# Sheet1.net
KiCad netlist of a schematic drawn in Altium Designer
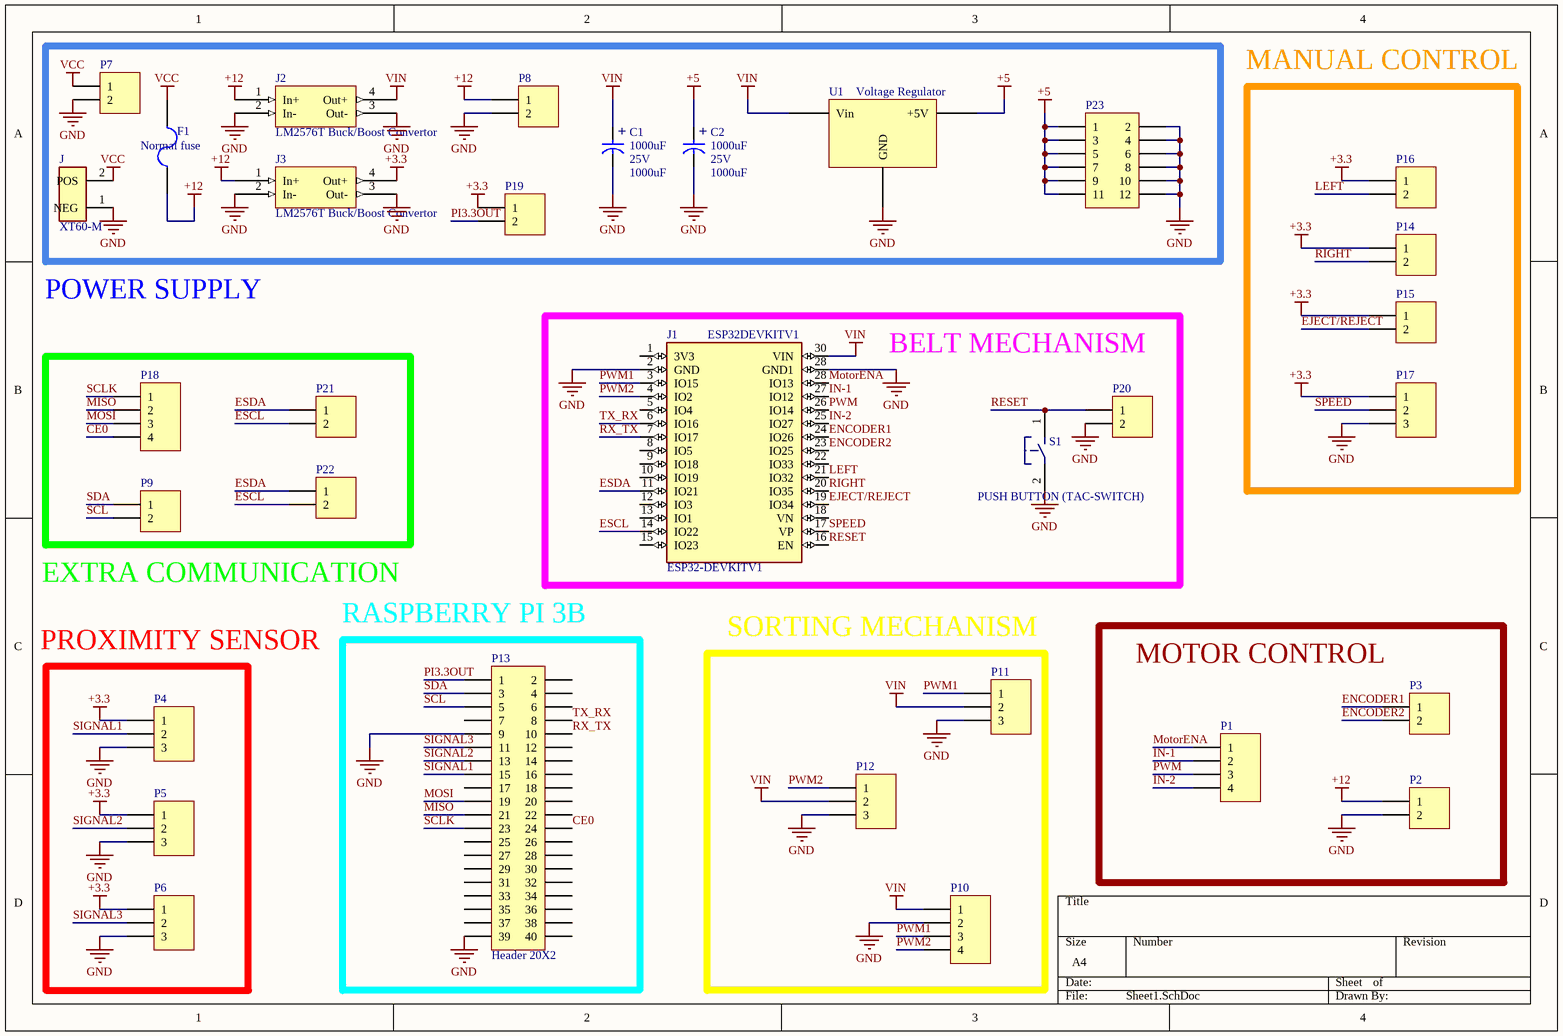
[diagram p0: Sheet1.SchDoc]

(export (version "E")
  (design (tool "Eeschema 10.0.6"))
  (components
    (comp (ref "C1")
      (value "1000uF")
      (footprint "SELF_CAP_THT5MM")
      (fields (field (name "VOLT") "25V") (field (name "ALTIUM_VALUE") "1000uF"))
      (libsource (lib "Webinar") (part "CAPACITOR (ELECTROLYTIC)"))
    )
    (comp (ref "C2")
      (value "1000uF")
      (footprint "SELF_CAP_THT5MM")
      (fields (field (name "VOLT") "25V") (field (name "ALTIUM_VALUE") "1000uF"))
      (libsource (lib "Webinar") (part "CAPACITOR (ELECTROLYTIC)"))
    )
    (comp (ref "F1")
      (value "Normal fuse")
      (footprint "MY_FUSE")
      (fields (field (name "ASID PART NUMBER") "Fuse-AS"))
      (libsource (lib "Mylib Rev 4") (part "Fuse"))
    )
    (comp (ref "J")
      (value "XT60-M")
      (footprint "AMASS_XT60-M")
      (description "Plug; DC supply; XT60; male; PIN: 2; for cable; soldered; 30A; 500V")
      (fields (field (name "MF") "AMASS"))
      (libsource (lib "myLibrary") (part "XT60-M"))
    )
    (comp (ref "J1")
      (value "ESP32DEVKITV1")
      (footprint "ESP32-DEVKITV1")
      (fields (field (name "MP") "ESP32 DEVKIT V1") (field (name "MF") "Do it"))
      (libsource (lib "ESP32DEVKITV1") (part "ESP32DEVKITV1"))
    )
    (comp (ref "J2")
      (value "LM2576T Buck/Boost Convertor")
      (footprint "LM2596 MODULE")
      (libsource (lib "myLibrary") (part "LM2576T Buck/Boost Convertor"))
    )
    (comp (ref "J3")
      (value "LM2576T Buck/Boost Convertor")
      (footprint "LM2596 MODULE")
      (libsource (lib "myLibrary") (part "LM2576T Buck/Boost Convertor"))
    )
    (comp (ref "P1")
      (value "Header 4")
      (footprint "MY_6410-04")
      (description "motor driver control pin")
      (fields (field (name "ASID PART NUMBER") "Header 4-AS"))
      (libsource (lib "Mylib Rev 4") (part "Header 4"))
    )
    (comp (ref "P2")
      (value "Header 2")
      (footprint "My_CN2")
      (description "motor driver power")
      (fields (field (name "ASID PART NUMBER") "Header 2-AS"))
      (libsource (lib "Mylib Rev 4") (part "Header 2"))
    )
    (comp (ref "P3")
      (value "Header 2")
      (footprint "MY_6410-02")
      (description "motor encoder")
      (fields (field (name "ASID PART NUMBER") "Header 2-AS"))
      (libsource (lib "Mylib Rev 4") (part "Header 2"))
    )
    (comp (ref "P4")
      (value "Header 3")
      (footprint "MY_6410-03")
      (description "PROXIMITY SENSOR 1")
      (fields (field (name "ASID PART NUMBER") "Header 3-AS"))
      (libsource (lib "Mylib Rev 4") (part "Header 3"))
    )
    (comp (ref "P5")
      (value "Header 3")
      (footprint "MY_6410-03")
      (description "PROXIMITY SENSOR 2")
      (fields (field (name "ASID PART NUMBER") "Header 3-AS"))
      (libsource (lib "Mylib Rev 4") (part "Header 3"))
    )
    (comp (ref "P6")
      (value "Header 3")
      (footprint "MY_6410-03")
      (description "PROXIMITY SENSOR 3")
      (fields (field (name "ASID PART NUMBER") "Header 3-AS"))
      (libsource (lib "Mylib Rev 4") (part "Header 3"))
    )
    (comp (ref "P7")
      (value "Header 2")
      (footprint "My_CN2")
      (description "power in")
      (fields (field (name "ASID PART NUMBER") "Header 2-AS"))
      (libsource (lib "Mylib Rev 4") (part "Header 2"))
    )
    (comp (ref "P8")
      (value "Header 2")
      (footprint "My_CN2")
      (description "led supply")
      (fields (field (name "ASID PART NUMBER") "Header 2-AS"))
      (libsource (lib "Mylib Rev 4") (part "Header 2"))
    )
    (comp (ref "P9")
      (value "Header 2")
      (footprint "MY_6410-02")
      (description "i2c port for future use.Raspberry pi 2b.")
      (fields (field (name "ASID PART NUMBER") "Header 2-AS"))
      (libsource (lib "Mylib Rev 4") (part "Header 2"))
    )
    (comp (ref "P10")
      (value "Header 4")
      (footprint "MY_6410-04")
      (description "SORTING MECHANISM for uln2003")
      (fields (field (name "ASID PART NUMBER") "Header 4-AS"))
      (libsource (lib "Mylib Rev 4") (part "Header 4"))
    )
    (comp (ref "P11")
      (value "Header 3")
      (footprint "MY_6410-03")
      (description "SORTING MECHANISM -servo motor 1")
      (fields (field (name "ASID PART NUMBER") "Header 3-AS"))
      (libsource (lib "Mylib Rev 4") (part "Header 3"))
    )
    (comp (ref "P12")
      (value "Header 3")
      (footprint "MY_6410-03")
      (description "SORTING MECHANISM -servo motor 2")
      (fields (field (name "ASID PART NUMBER") "Header 3-AS"))
      (libsource (lib "Mylib Rev 4") (part "Header 3"))
    )
    (comp (ref "P13")
      (value "Header 20X2")
      (footprint "MY_2X20")
      (description "rasbery pi 2 b connector")
      (fields (field (name "ASID PART NUMBER") "Header 20X2-AS"))
      (libsource (lib "Mylib Rev 4") (part "Header 20X2"))
    )
    (comp (ref "P14")
      (value "Header 2")
      (footprint "MY_6410-02")
      (description "manual control switch2")
      (fields (field (name "ASID PART NUMBER") "Header 2-AS"))
      (libsource (lib "Mylib Rev 4") (part "Header 2"))
    )
    (comp (ref "P15")
      (value "Header 2")
      (footprint "MY_6410-02")
      (description "manual control switch3")
      (fields (field (name "ASID PART NUMBER") "Header 2-AS"))
      (libsource (lib "Mylib Rev 4") (part "Header 2"))
    )
    (comp (ref "P16")
      (value "Header 2")
      (footprint "MY_6410-02")
      (description "manual control switch1")
      (fields (field (name "ASID PART NUMBER") "Header 2-AS"))
      (libsource (lib "Mylib Rev 4") (part "Header 2"))
    )
    (comp (ref "P17")
      (value "Header 3")
      (footprint "MY_6410-03")
      (description "manual control - speed")
      (fields (field (name "ASID PART NUMBER") "Header 3-AS"))
      (libsource (lib "Mylib Rev 4") (part "Header 3"))
    )
    (comp (ref "P18")
      (value "Header 4")
      (footprint "MY_6410-04")
      (description "SPI for future use. raspberry pi 2b")
      (fields (field (name "ASID PART NUMBER") "Header 4-AS"))
      (libsource (lib "Mylib Rev 4") (part "Header 4"))
    )
    (comp (ref "P19")
      (value "Header 2")
      (footprint "My_1X02")
      (description "selection of pi 3.3v power out")
      (fields (field (name "ASID PART NUMBER") "Header 2-AS"))
      (libsource (lib "Mylib Rev 4") (part "Header 2"))
    )
    (comp (ref "P20")
      (value "Header 2")
      (footprint "MY_6410-02")
      (description "EXTERNAL RESET")
      (fields (field (name "ASID PART NUMBER") "Header 2-AS"))
      (libsource (lib "Mylib Rev 4") (part "Header 2"))
    )
    (comp (ref "P21")
      (value "Header 2")
      (footprint "MY_6410-02")
      (description "I2C of esp32 port 1")
      (fields (field (name "ASID PART NUMBER") "Header 2-AS"))
      (libsource (lib "Mylib Rev 4") (part "Header 2"))
    )
    (comp (ref "P22")
      (value "Header 2")
      (footprint "MY_6410-02")
      (description "I2C of esp32 port 2")
      (fields (field (name "ASID PART NUMBER") "Header 2-AS"))
      (libsource (lib "Mylib Rev 4") (part "Header 2"))
    )
    (comp (ref "P23")
      (value "Header 6X2")
      (footprint "My_2X06")
      (description "Header, 12-Pin, Dual row")
      (fields (field (name "ASID PART NUMBER") "Header 6X2-AS"))
      (libsource (lib "Mylib Rev 4") (part "Header 6X2"))
    )
    (comp (ref "S1")
      (value "PUSH BUTTON (TAC-SWITCH)")
      (footprint "SELF_TACTILE_THT")
      (libsource (lib "Webinar") (part "PUSH BUTTON (TAC-SWITCH)"))
    )
    (comp (ref "U1")
      (value "Voltage Regulator")
      (footprint "SELF_LM7805_THT")
      (description "+5v voltage regulator")
      (libsource (lib "Webinar") (part "LM7805"))
    )
  )
  (nets
    (net (code "1") (name "+3.3") (class "Default")
      (node (ref "J3") (pin "4") (pinfunction "Out+_4") (pintype "output"))
      (node (ref "P14") (pin "1") (pinfunction "1_1") (pintype "passive"))
      (node (ref "P15") (pin "1") (pinfunction "1_1") (pintype "passive"))
      (node (ref "P16") (pin "1") (pinfunction "1_1") (pintype "passive"))
      (node (ref "P17") (pin "1") (pinfunction "1_1") (pintype "passive"))
      (node (ref "P19") (pin "1") (pinfunction "1_1") (pintype "passive"))
      (node (ref "P4") (pin "1") (pinfunction "1_1") (pintype "passive"))
      (node (ref "P5") (pin "1") (pinfunction "1_1") (pintype "passive"))
      (node (ref "P6") (pin "1") (pinfunction "1_1") (pintype "passive"))
    )
    (net (code "2") (name "+5") (class "Default")
      (node (ref "C2") (pin "+") (pinfunction "+_+") (pintype "passive"))
      (node (ref "P23") (pin "1") (pinfunction "1_1") (pintype "passive"))
      (node (ref "P23") (pin "11") (pinfunction "11_11") (pintype "passive"))
      (node (ref "P23") (pin "3") (pinfunction "3_3") (pintype "passive"))
      (node (ref "P23") (pin "5") (pinfunction "5_5") (pintype "passive"))
      (node (ref "P23") (pin "7") (pinfunction "7_7") (pintype "passive"))
      (node (ref "P23") (pin "9") (pinfunction "9_9") (pintype "passive"))
      (node (ref "U1") (pin "3") (pinfunction "+5V_3") (pintype "power_in"))
    )
    (net (code "3") (name "+12") (class "Default")
      (node (ref "F1") (pin "1") (pinfunction "1_1") (pintype "passive"))
      (node (ref "J2") (pin "1") (pinfunction "In+_1") (pintype "input"))
      (node (ref "J3") (pin "1") (pinfunction "In+_1") (pintype "input"))
      (node (ref "P2") (pin "1") (pinfunction "1_1") (pintype "passive"))
      (node (ref "P8") (pin "1") (pinfunction "1_1") (pintype "passive"))
    )
    (net (code "4") (name "/CE0") (class "Default")
      (node (ref "P13") (pin "24") (pinfunction "24_24") (pintype "passive"))
      (node (ref "P18") (pin "4") (pinfunction "4_4") (pintype "passive"))
    )
    (net (code "5") (name "/EJECT{slash}REJECT") (class "Default")
      (node (ref "J1") (pin "19") (pinfunction "IO34_19") (pintype "bidirectional"))
      (node (ref "P15") (pin "2") (pinfunction "2_2") (pintype "passive"))
    )
    (net (code "6") (name "/ENCODER1") (class "Default")
      (node (ref "J1") (pin "24") (pinfunction "IO26_24") (pintype "bidirectional"))
      (node (ref "P3") (pin "1") (pinfunction "1_1") (pintype "passive"))
    )
    (net (code "7") (name "/ENCODER2") (class "Default")
      (node (ref "J1") (pin "23") (pinfunction "IO25_23") (pintype "bidirectional"))
      (node (ref "P3") (pin "2") (pinfunction "2_2") (pintype "passive"))
    )
    (net (code "8") (name "/ESCL") (class "Default")
      (node (ref "J1") (pin "14") (pinfunction "IO22_14") (pintype "bidirectional"))
      (node (ref "P21") (pin "2") (pinfunction "2_2") (pintype "passive"))
      (node (ref "P22") (pin "2") (pinfunction "2_2") (pintype "passive"))
    )
    (net (code "9") (name "/ESDA") (class "Default")
      (node (ref "J1") (pin "11") (pinfunction "IO21_11") (pintype "bidirectional"))
      (node (ref "P21") (pin "1") (pinfunction "1_1") (pintype "passive"))
      (node (ref "P22") (pin "1") (pinfunction "1_1") (pintype "passive"))
    )
    (net (code "10") (name "/IN-1") (class "Default")
      (node (ref "J1") (pin "27") (pinfunction "IO12_27") (pintype "bidirectional"))
      (node (ref "P1") (pin "2") (pinfunction "2_2") (pintype "passive"))
    )
    (net (code "11") (name "/IN-2") (class "Default")
      (node (ref "J1") (pin "25") (pinfunction "IO27_25") (pintype "bidirectional"))
      (node (ref "P1") (pin "4") (pinfunction "4_4") (pintype "passive"))
    )
    (net (code "12") (name "/LEFT") (class "Default")
      (node (ref "J1") (pin "21") (pinfunction "IO32_21") (pintype "bidirectional"))
      (node (ref "P16") (pin "2") (pinfunction "2_2") (pintype "passive"))
    )
    (net (code "13") (name "/MISO") (class "Default")
      (node (ref "P13") (pin "21") (pinfunction "21_21") (pintype "passive"))
      (node (ref "P18") (pin "2") (pinfunction "2_2") (pintype "passive"))
    )
    (net (code "14") (name "/MOSI") (class "Default")
      (node (ref "P13") (pin "19") (pinfunction "19_19") (pintype "passive"))
      (node (ref "P18") (pin "3") (pinfunction "3_3") (pintype "passive"))
    )
    (net (code "15") (name "/MotorENA") (class "Default")
      (node (ref "J1") (pin "28") (pinfunction "IO13_28") (pintype "bidirectional"))
      (node (ref "P1") (pin "1") (pinfunction "1_1") (pintype "passive"))
    )
    (net (code "16") (name "/PI3.3OUT") (class "Default")
      (node (ref "P13") (pin "1") (pinfunction "1_1") (pintype "passive"))
      (node (ref "P19") (pin "2") (pinfunction "2_2") (pintype "passive"))
    )
    (net (code "17") (name "/PWM") (class "Default")
      (node (ref "J1") (pin "26") (pinfunction "IO14_26") (pintype "bidirectional"))
      (node (ref "P1") (pin "3") (pinfunction "3_3") (pintype "passive"))
    )
    (net (code "18") (name "/PWM1") (class "Default")
      (node (ref "J1") (pin "3") (pinfunction "IO15_3") (pintype "bidirectional"))
      (node (ref "P10") (pin "3") (pinfunction "3_3") (pintype "passive"))
      (node (ref "P11") (pin "1") (pinfunction "1_1") (pintype "passive"))
    )
    (net (code "19") (name "/PWM2") (class "Default")
      (node (ref "J1") (pin "4") (pinfunction "IO2_4") (pintype "bidirectional"))
      (node (ref "P10") (pin "4") (pinfunction "4_4") (pintype "passive"))
      (node (ref "P12") (pin "1") (pinfunction "1_1") (pintype "passive"))
    )
    (net (code "20") (name "/RESET") (class "Default")
      (node (ref "J1") (pin "16") (pinfunction "EN_16") (pintype "bidirectional"))
      (node (ref "P20") (pin "1") (pinfunction "1_1") (pintype "passive"))
      (node (ref "S1") (pin "1") (pinfunction "1_1") (pintype "passive"))
    )
    (net (code "21") (name "/RIGHT") (class "Default")
      (node (ref "J1") (pin "20") (pinfunction "IO35_20") (pintype "bidirectional"))
      (node (ref "P14") (pin "2") (pinfunction "2_2") (pintype "passive"))
    )
    (net (code "22") (name "/RX_TX") (class "Default")
      (node (ref "J1") (pin "7") (pinfunction "IO17_7") (pintype "bidirectional"))
      (node (ref "P13") (pin "10") (pinfunction "10_10") (pintype "passive"))
    )
    (net (code "23") (name "/SCL") (class "Default")
      (node (ref "P13") (pin "5") (pinfunction "5_5") (pintype "passive"))
      (node (ref "P9") (pin "2") (pinfunction "2_2") (pintype "passive"))
    )
    (net (code "24") (name "/SCLK") (class "Default")
      (node (ref "P13") (pin "23") (pinfunction "23_23") (pintype "passive"))
      (node (ref "P18") (pin "1") (pinfunction "1_1") (pintype "passive"))
    )
    (net (code "25") (name "/SDA") (class "Default")
      (node (ref "P13") (pin "3") (pinfunction "3_3") (pintype "passive"))
      (node (ref "P9") (pin "1") (pinfunction "1_1") (pintype "passive"))
    )
    (net (code "26") (name "/SIGNAL1") (class "Default")
      (node (ref "P13") (pin "15") (pinfunction "15_15") (pintype "passive"))
      (node (ref "P4") (pin "2") (pinfunction "2_2") (pintype "passive"))
    )
    (net (code "27") (name "/SIGNAL2") (class "Default")
      (node (ref "P13") (pin "13") (pinfunction "13_13") (pintype "passive"))
      (node (ref "P5") (pin "2") (pinfunction "2_2") (pintype "passive"))
    )
    (net (code "28") (name "/SIGNAL3") (class "Default")
      (node (ref "P13") (pin "11") (pinfunction "11_11") (pintype "passive"))
      (node (ref "P6") (pin "2") (pinfunction "2_2") (pintype "passive"))
    )
    (net (code "29") (name "/SPEED") (class "Default")
      (node (ref "J1") (pin "17") (pinfunction "VP_17") (pintype "bidirectional"))
      (node (ref "P17") (pin "2") (pinfunction "2_2") (pintype "passive"))
    )
    (net (code "30") (name "/TX_RX") (class "Default")
      (node (ref "J1") (pin "6") (pinfunction "IO16_6") (pintype "bidirectional"))
      (node (ref "P13") (pin "8") (pinfunction "8_8") (pintype "passive"))
    )
    (net (code "31") (name "GND") (class "Default")
      (node (ref "C1") (pin "-") (pinfunction "-_-") (pintype "passive"))
      (node (ref "C2") (pin "-") (pinfunction "-_-") (pintype "passive"))
      (node (ref "J") (pin "1") (pinfunction "NEG_1") (pintype "passive"))
      (node (ref "J1") (pin "2") (pinfunction "GND_2") (pintype "bidirectional"))
      (node (ref "J1") (pin "28") (pinfunction "GND1_28") (pintype "bidirectional"))
      (node (ref "J2") (pin "2") (pinfunction "In-_2") (pintype "input"))
      (node (ref "J2") (pin "3") (pinfunction "Out-_3") (pintype "output"))
      (node (ref "J3") (pin "2") (pinfunction "In-_2") (pintype "input"))
      (node (ref "J3") (pin "3") (pinfunction "Out-_3") (pintype "output"))
      (node (ref "P10") (pin "2") (pinfunction "2_2") (pintype "passive"))
      (node (ref "P11") (pin "3") (pinfunction "3_3") (pintype "passive"))
      (node (ref "P12") (pin "3") (pinfunction "3_3") (pintype "passive"))
      (node (ref "P13") (pin "39") (pinfunction "39_39") (pintype "passive"))
      (node (ref "P13") (pin "9") (pinfunction "9_9") (pintype "passive"))
      (node (ref "P17") (pin "3") (pinfunction "3_3") (pintype "passive"))
      (node (ref "P2") (pin "2") (pinfunction "2_2") (pintype "passive"))
      (node (ref "P20") (pin "2") (pinfunction "2_2") (pintype "passive"))
      (node (ref "P23") (pin "10") (pinfunction "10_10") (pintype "passive"))
      (node (ref "P23") (pin "12") (pinfunction "12_12") (pintype "passive"))
      (node (ref "P23") (pin "2") (pinfunction "2_2") (pintype "passive"))
      (node (ref "P23") (pin "4") (pinfunction "4_4") (pintype "passive"))
      (node (ref "P23") (pin "6") (pinfunction "6_6") (pintype "passive"))
      (node (ref "P23") (pin "8") (pinfunction "8_8") (pintype "passive"))
      (node (ref "P4") (pin "3") (pinfunction "3_3") (pintype "passive"))
      (node (ref "P5") (pin "3") (pinfunction "3_3") (pintype "passive"))
      (node (ref "P6") (pin "3") (pinfunction "3_3") (pintype "passive"))
      (node (ref "P7") (pin "2") (pinfunction "2_2") (pintype "passive"))
      (node (ref "P8") (pin "2") (pinfunction "2_2") (pintype "passive"))
      (node (ref "S1") (pin "2") (pinfunction "2_2") (pintype "passive"))
      (node (ref "U1") (pin "2") (pinfunction "GND_2") (pintype "power_in"))
    )
    (net (code "32") (name "VCC") (class "Default")
      (node (ref "F1") (pin "2") (pinfunction "2_2") (pintype "passive"))
      (node (ref "J") (pin "2") (pinfunction "POS_2") (pintype "passive"))
      (node (ref "P7") (pin "1") (pinfunction "1_1") (pintype "passive"))
    )
    (net (code "33") (name "VIN") (class "Default")
      (node (ref "C1") (pin "+") (pinfunction "+_+") (pintype "passive"))
      (node (ref "J1") (pin "30") (pinfunction "VIN_30") (pintype "bidirectional"))
      (node (ref "J2") (pin "4") (pinfunction "Out+_4") (pintype "output"))
      (node (ref "P10") (pin "1") (pinfunction "1_1") (pintype "passive"))
      (node (ref "P11") (pin "2") (pinfunction "2_2") (pintype "passive"))
      (node (ref "P12") (pin "2") (pinfunction "2_2") (pintype "passive"))
      (node (ref "U1") (pin "1") (pinfunction "Vin_1") (pintype "power_in"))
    )
    (net (code "34") (name "unconnected-(J1-3V3-Pad1)") (class "Default")
      (node (ref "J1") (pin "1") (pinfunction "3V3_1") (pintype "bidirectional"))
    )
    (net (code "35") (name "unconnected-(J1-IO1-Pad13)") (class "Default")
      (node (ref "J1") (pin "13") (pinfunction "IO1_13") (pintype "bidirectional"))
    )
    (net (code "36") (name "unconnected-(J1-IO3-Pad12)") (class "Default")
      (node (ref "J1") (pin "12") (pinfunction "IO3_12") (pintype "bidirectional"))
    )
    (net (code "37") (name "unconnected-(J1-IO4-Pad5)") (class "Default")
      (node (ref "J1") (pin "5") (pinfunction "IO4_5") (pintype "bidirectional"))
    )
    (net (code "38") (name "unconnected-(J1-IO5-Pad8)") (class "Default")
      (node (ref "J1") (pin "8") (pinfunction "IO5_8") (pintype "bidirectional"))
    )
    (net (code "39") (name "unconnected-(J1-IO18-Pad9)") (class "Default")
      (node (ref "J1") (pin "9") (pinfunction "IO18_9") (pintype "bidirectional"))
    )
    (net (code "40") (name "unconnected-(J1-IO19-Pad10)") (class "Default")
      (node (ref "J1") (pin "10") (pinfunction "IO19_10") (pintype "bidirectional"))
    )
    (net (code "41") (name "unconnected-(J1-IO23-Pad15)") (class "Default")
      (node (ref "J1") (pin "15") (pinfunction "IO23_15") (pintype "bidirectional"))
    )
    (net (code "42") (name "unconnected-(J1-IO33-Pad22)") (class "Default")
      (node (ref "J1") (pin "22") (pinfunction "IO33_22") (pintype "bidirectional"))
    )
    (net (code "43") (name "unconnected-(J1-VN-Pad18)") (class "Default")
      (node (ref "J1") (pin "18") (pinfunction "VN_18") (pintype "bidirectional"))
    )
    (net (code "44") (name "unconnected-(P13-Pad2)") (class "Default")
      (node (ref "P13") (pin "2") (pinfunction "2_2") (pintype "passive"))
    )
    (net (code "45") (name "unconnected-(P13-Pad4)") (class "Default")
      (node (ref "P13") (pin "4") (pinfunction "4_4") (pintype "passive"))
    )
    (net (code "46") (name "unconnected-(P13-Pad6)") (class "Default")
      (node (ref "P13") (pin "6") (pinfunction "6_6") (pintype "passive"))
    )
    (net (code "47") (name "unconnected-(P13-Pad7)") (class "Default")
      (node (ref "P13") (pin "7") (pinfunction "7_7") (pintype "passive"))
    )
    (net (code "48") (name "unconnected-(P13-Pad12)") (class "Default")
      (node (ref "P13") (pin "12") (pinfunction "12_12") (pintype "passive"))
    )
    (net (code "49") (name "unconnected-(P13-Pad14)") (class "Default")
      (node (ref "P13") (pin "14") (pinfunction "14_14") (pintype "passive"))
    )
    (net (code "50") (name "unconnected-(P13-Pad16)") (class "Default")
      (node (ref "P13") (pin "16") (pinfunction "16_16") (pintype "passive"))
    )
    (net (code "51") (name "unconnected-(P13-Pad17)") (class "Default")
      (node (ref "P13") (pin "17") (pinfunction "17_17") (pintype "passive"))
    )
    (net (code "52") (name "unconnected-(P13-Pad18)") (class "Default")
      (node (ref "P13") (pin "18") (pinfunction "18_18") (pintype "passive"))
    )
    (net (code "53") (name "unconnected-(P13-Pad20)") (class "Default")
      (node (ref "P13") (pin "20") (pinfunction "20_20") (pintype "passive"))
    )
    (net (code "54") (name "unconnected-(P13-Pad22)") (class "Default")
      (node (ref "P13") (pin "22") (pinfunction "22_22") (pintype "passive"))
    )
    (net (code "55") (name "unconnected-(P13-Pad25)") (class "Default")
      (node (ref "P13") (pin "25") (pinfunction "25_25") (pintype "passive"))
    )
    (net (code "56") (name "unconnected-(P13-Pad26)") (class "Default")
      (node (ref "P13") (pin "26") (pinfunction "26_26") (pintype "passive"))
    )
    (net (code "57") (name "unconnected-(P13-Pad27)") (class "Default")
      (node (ref "P13") (pin "27") (pinfunction "27_27") (pintype "passive"))
    )
    (net (code "58") (name "unconnected-(P13-Pad28)") (class "Default")
      (node (ref "P13") (pin "28") (pinfunction "28_28") (pintype "passive"))
    )
    (net (code "59") (name "unconnected-(P13-Pad29)") (class "Default")
      (node (ref "P13") (pin "29") (pinfunction "29_29") (pintype "passive"))
    )
    (net (code "60") (name "unconnected-(P13-Pad30)") (class "Default")
      (node (ref "P13") (pin "30") (pinfunction "30_30") (pintype "passive"))
    )
    (net (code "61") (name "unconnected-(P13-Pad31)") (class "Default")
      (node (ref "P13") (pin "31") (pinfunction "31_31") (pintype "passive"))
    )
    (net (code "62") (name "unconnected-(P13-Pad32)") (class "Default")
      (node (ref "P13") (pin "32") (pinfunction "32_32") (pintype "passive"))
    )
    (net (code "63") (name "unconnected-(P13-Pad33)") (class "Default")
      (node (ref "P13") (pin "33") (pinfunction "33_33") (pintype "passive"))
    )
    (net (code "64") (name "unconnected-(P13-Pad34)") (class "Default")
      (node (ref "P13") (pin "34") (pinfunction "34_34") (pintype "passive"))
    )
    (net (code "65") (name "unconnected-(P13-Pad35)") (class "Default")
      (node (ref "P13") (pin "35") (pinfunction "35_35") (pintype "passive"))
    )
    (net (code "66") (name "unconnected-(P13-Pad36)") (class "Default")
      (node (ref "P13") (pin "36") (pinfunction "36_36") (pintype "passive"))
    )
    (net (code "67") (name "unconnected-(P13-Pad37)") (class "Default")
      (node (ref "P13") (pin "37") (pinfunction "37_37") (pintype "passive"))
    )
    (net (code "68") (name "unconnected-(P13-Pad38)") (class "Default")
      (node (ref "P13") (pin "38") (pinfunction "38_38") (pintype "passive"))
    )
    (net (code "69") (name "unconnected-(P13-Pad40)") (class "Default")
      (node (ref "P13") (pin "40") (pinfunction "40_40") (pintype "passive"))
    )
  )
)
